# FT2232H.net
KiCad netlist of a schematic drawn in Altium Designer
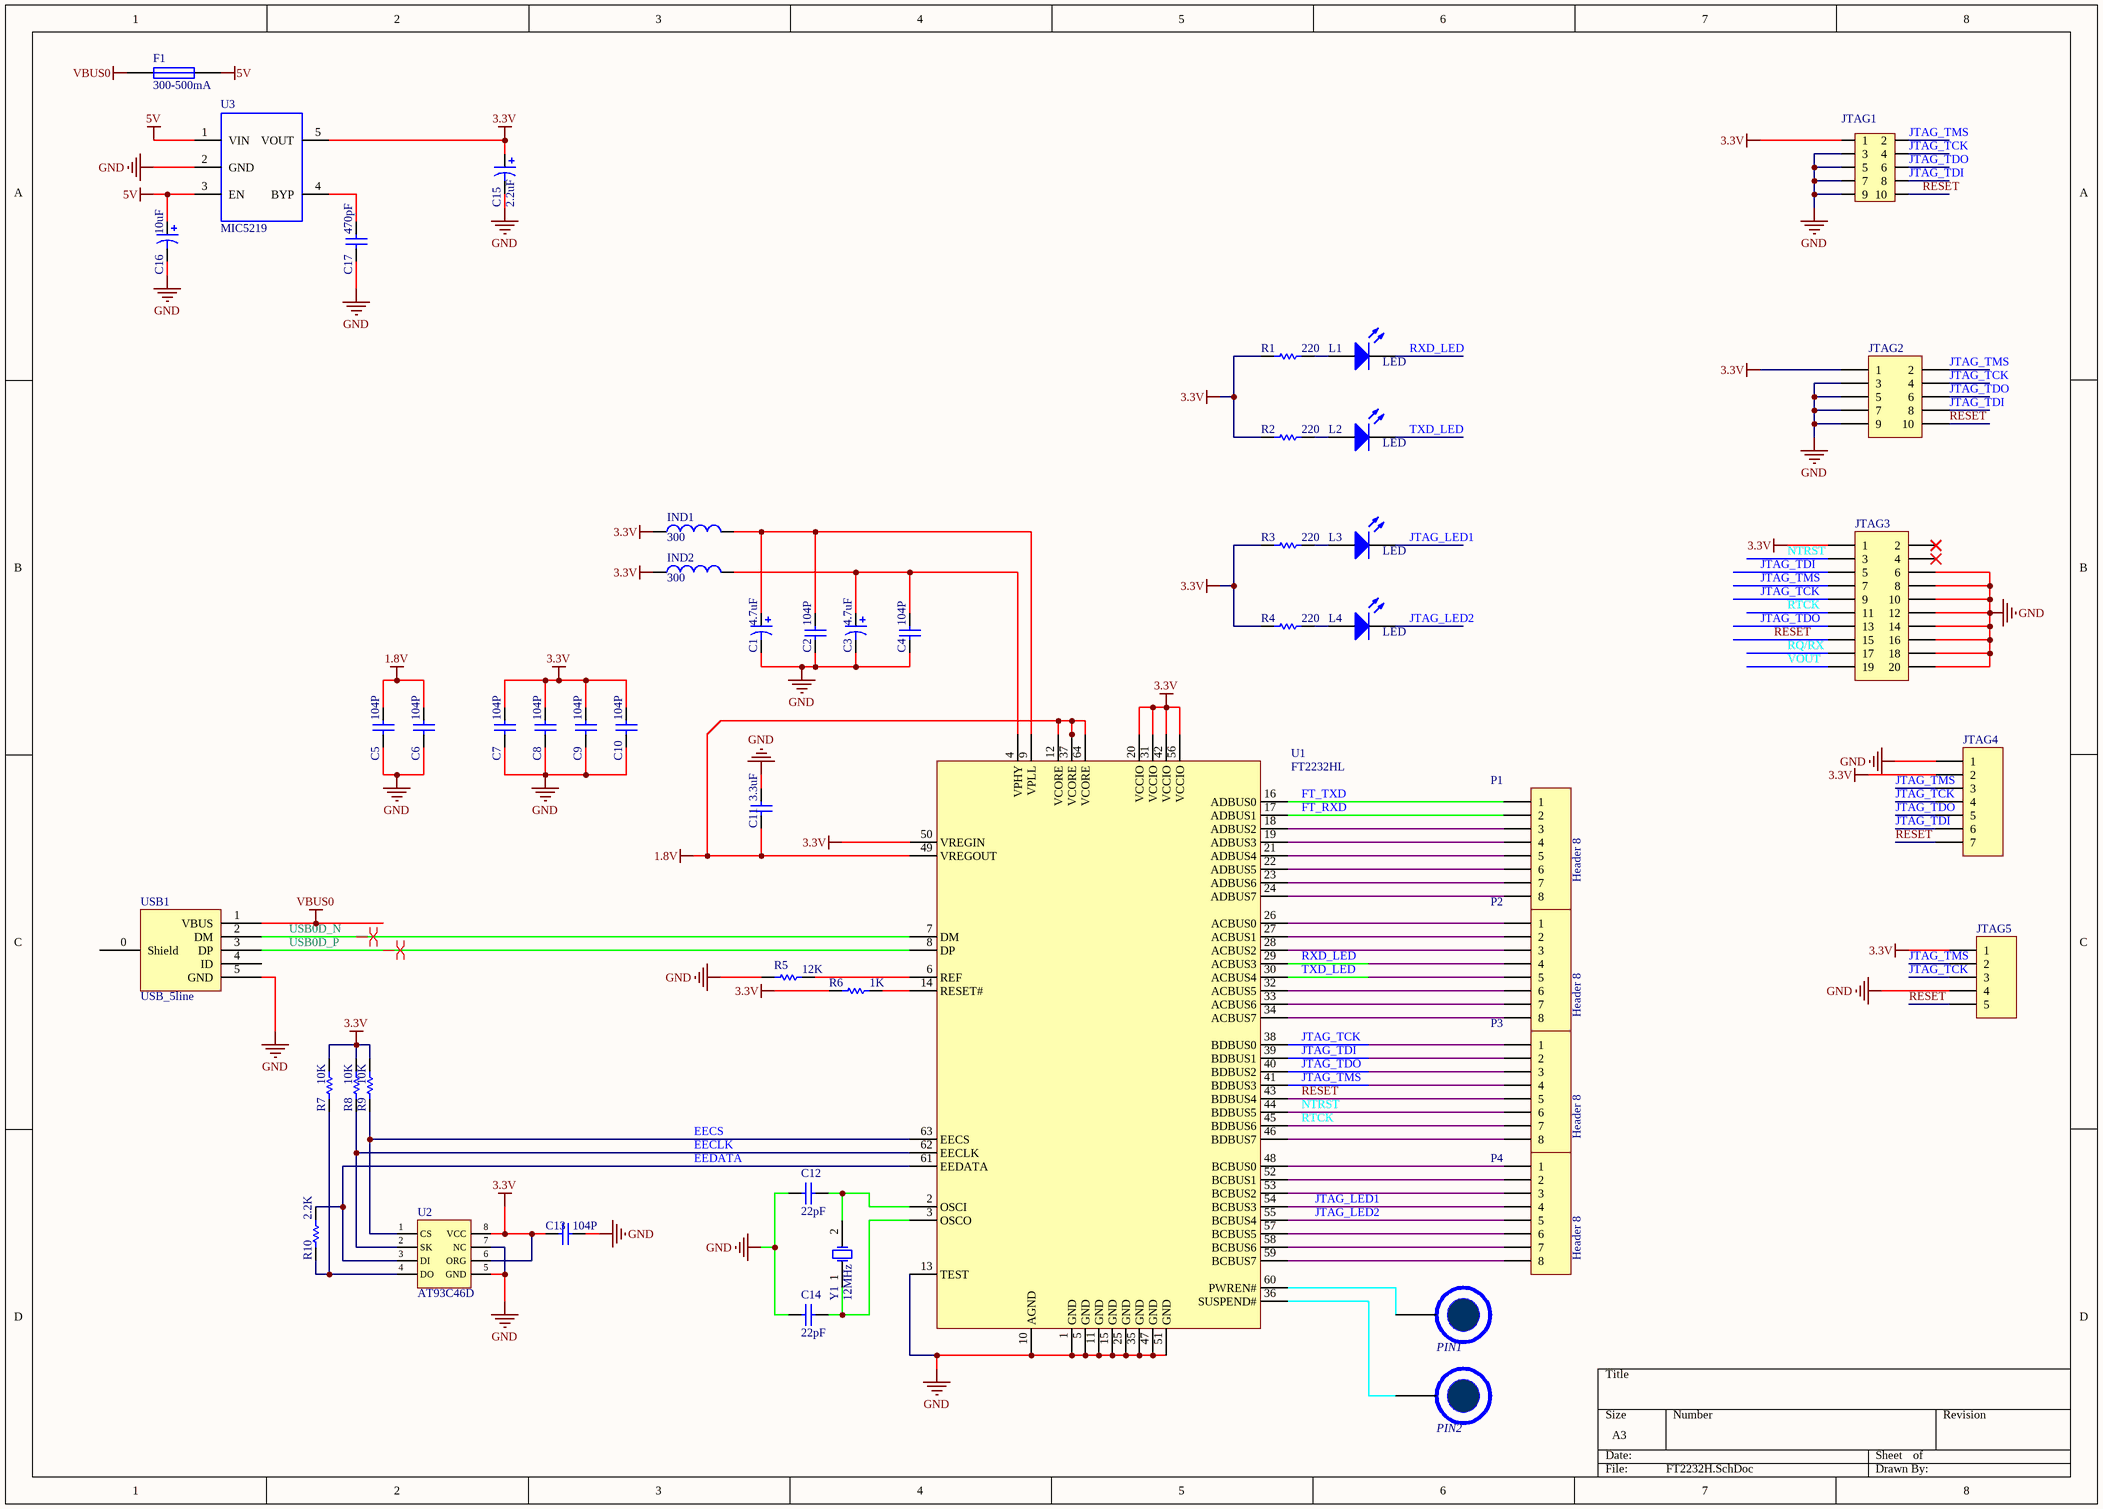
[diagram p0: FT2232H.SchDoc]

(export (version "E")
  (design (tool "Eeschema 10.0.6"))
  (components
    (comp (ref "C1")
      (value "4.7uF")
      (footprint "1608[0603]")
      (description "Polarized Capacitor (Radial)")
      (fields (field (name "Comment") "Cap Pol1") (field (name "PUBLISHER") "Altium Limited"))
      (libsource (lib "Miscellaneous Devices") (part "Cap Pol1"))
    )
    (comp (ref "C2")
      (value "104P")
      (footprint "1608[0603]")
      (description "贴片电容")
      (fields (field (name "Comment") "Cap") (field (name "PUBLISHER") "Altium Limited"))
      (libsource (lib "Sparks") (part "Cap"))
    )
    (comp (ref "C3")
      (value "4.7uF")
      (footprint "1608[0603]")
      (description "Polarized Capacitor (Radial)")
      (fields (field (name "Comment") "Cap Pol1") (field (name "PUBLISHER") "Altium Limited"))
      (libsource (lib "Miscellaneous Devices") (part "Cap Pol1"))
    )
    (comp (ref "C4")
      (value "104P")
      (footprint "1608[0603]")
      (description "贴片电容")
      (fields (field (name "Comment") "Cap") (field (name "PUBLISHER") "Altium Limited"))
      (libsource (lib "Sparks") (part "Cap"))
    )
    (comp (ref "C5")
      (value "104P")
      (footprint "1608[0603]")
      (description "贴片电容")
      (fields (field (name "Comment") "Cap") (field (name "PUBLISHER") "Altium Limited"))
      (libsource (lib "Sparks") (part "Cap"))
    )
    (comp (ref "C6")
      (value "104P")
      (footprint "1608[0603]")
      (description "贴片电容")
      (fields (field (name "Comment") "Cap") (field (name "PUBLISHER") "Altium Limited"))
      (libsource (lib "Sparks") (part "Cap"))
    )
    (comp (ref "C7")
      (value "104P")
      (footprint "1608[0603]")
      (description "贴片电容")
      (fields (field (name "Comment") "Cap") (field (name "PUBLISHER") "Altium Limited"))
      (libsource (lib "Sparks") (part "Cap"))
    )
    (comp (ref "C8")
      (value "104P")
      (footprint "1608[0603]")
      (description "贴片电容")
      (fields (field (name "Comment") "Cap") (field (name "PUBLISHER") "Altium Limited"))
      (libsource (lib "Sparks") (part "Cap"))
    )
    (comp (ref "C9")
      (value "104P")
      (footprint "1608[0603]")
      (description "贴片电容")
      (fields (field (name "Comment") "Cap") (field (name "PUBLISHER") "Altium Limited"))
      (libsource (lib "Sparks") (part "Cap"))
    )
    (comp (ref "C10")
      (value "104P")
      (footprint "1608[0603]")
      (description "贴片电容")
      (fields (field (name "Comment") "Cap") (field (name "PUBLISHER") "Altium Limited"))
      (libsource (lib "Sparks") (part "Cap"))
    )
    (comp (ref "C11")
      (value "3.3uF")
      (footprint "1608[0603]")
      (description "贴片电容")
      (fields (field (name "Comment") "Cap") (field (name "PUBLISHER") "Altium Limited"))
      (libsource (lib "Sparks") (part "Cap"))
    )
    (comp (ref "C12")
      (value "22pF")
      (footprint "1608[0603]")
      (description "贴片电容")
      (fields (field (name "Comment") "Cap") (field (name "PUBLISHER") "Altium Limited"))
      (libsource (lib "Sparks") (part "Cap"))
    )
    (comp (ref "C13")
      (value "104P")
      (footprint "1608[0603]")
      (description "贴片电容")
      (fields (field (name "Comment") "Cap") (field (name "PUBLISHER") "Altium Limited"))
      (libsource (lib "Sparks") (part "Cap"))
    )
    (comp (ref "C14")
      (value "22pF")
      (footprint "1608[0603]")
      (description "贴片电容")
      (fields (field (name "Comment") "Cap") (field (name "PUBLISHER") "Altium Limited"))
      (libsource (lib "Sparks") (part "Cap"))
    )
    (comp (ref "C15")
      (value "2.2uF")
      (footprint "1206(2)")
      (description "Polarized Capacitor (Radial)")
      (fields (field (name "Comment") "Cap Pol1") (field (name "PUBLISHER") "Altium Limited"))
      (libsource (lib "Miscellaneous Devices") (part "Cap Pol1"))
    )
    (comp (ref "C16")
      (value "10uF")
      (footprint "1206(2)")
      (description "Polarized Capacitor (Radial)")
      (fields (field (name "Comment") "Cap Pol1") (field (name "PUBLISHER") "Altium Limited"))
      (libsource (lib "Miscellaneous Devices") (part "Cap Pol1"))
    )
    (comp (ref "C17")
      (value "470pF")
      (footprint "1608[0603]")
      (description "贴片电容")
      (fields (field (name "Comment") "Cap") (field (name "PUBLISHER") "Altium Limited"))
      (libsource (lib "Sparks") (part "Cap"))
    )
    (comp (ref "F1")
      (value "300-500mA")
      (footprint "1206(2)")
      (description "Fuse")
      (fields (field (name "PUBLISHER") "Altium Limited"))
      (libsource (lib "K60-V4.0") (part "Fuse 1"))
    )
    (comp (ref "IND1")
      (value "300")
      (footprint "1608[0603]")
      (description "Inductor")
      (fields (field (name "PUBLISHER") "Altium Limited"))
      (libsource (lib "Miscellaneous Devices") (part "Inductor"))
    )
    (comp (ref "IND2")
      (value "300")
      (footprint "1608[0603]")
      (description "Inductor")
      (fields (field (name "PUBLISHER") "Altium Limited"))
      (libsource (lib "Miscellaneous Devices") (part "Inductor"))
    )
    (comp (ref "JTAG1")
      (value "Header 5X2")
      (footprint "IDC5X2")
      (description "Header, 5-Pin, Dual row")
      (libsource (lib "K60-V4.0") (part "Header 5X2"))
    )
    (comp (ref "JTAG2")
      (value "MHDR2X5")
      (footprint "MHDR2X5")
      (description "Header, 5-Pin, Dual row")
      (fields (field (name "PUBLISHER") "Altium Limited"))
      (libsource (lib "Miscellaneous Connectors") (part "MHDR2X5"))
    )
    (comp (ref "JTAG3")
      (value "Header 10X2")
      (footprint "HDR2X10")
      (description "Header, 10-Pin, Dual row")
      (fields (field (name "PUBLISHER") "Altium Limited"))
      (libsource (lib "Sparks") (part "Header 10X2"))
    )
    (comp (ref "JTAG4")
      (value "MHDR1X7")
      (footprint "MHDR1X7")
      (description "Header, 7-Pin")
      (fields (field (name "PUBLISHER") "Altium Limited"))
      (libsource (lib "Miscellaneous Connectors") (part "MHDR1X7"))
    )
    (comp (ref "JTAG5")
      (value "Header 5")
      (footprint "HDR1X5")
      (description "Header, 5-Pin")
      (fields (field (name "PUBLISHER") "Altium Limited"))
      (libsource (lib "Miscellaneous Connectors") (part "Header 5"))
    )
    (comp (ref "L1") (value "LED") (footprint "1608[0603]") (libsource (lib "Sparks") (part "LED")))
    (comp (ref "L2") (value "LED") (footprint "1608[0603]") (libsource (lib "Sparks") (part "LED")))
    (comp (ref "L3") (value "LED") (footprint "1608[0603]") (libsource (lib "Sparks") (part "LED")))
    (comp (ref "L4") (value "LED") (footprint "1608[0603]") (libsource (lib "Sparks") (part "LED")))
    (comp (ref "P1")
      (value "Header 8")
      (footprint "HDR1X8")
      (description "Header, 8-Pin")
      (fields (field (name "PUBLISHER") "Altium Limited"))
      (libsource (lib "Sparks") (part "Header 8"))
    )
    (comp (ref "P2")
      (value "Header 8")
      (footprint "HDR1X8")
      (description "Header, 8-Pin")
      (fields (field (name "PUBLISHER") "Altium Limited"))
      (libsource (lib "Sparks") (part "Header 8"))
    )
    (comp (ref "P3")
      (value "Header 8")
      (footprint "HDR1X8")
      (description "Header, 8-Pin")
      (fields (field (name "PUBLISHER") "Altium Limited"))
      (libsource (lib "Sparks") (part "Header 8"))
    )
    (comp (ref "P4")
      (value "Header 8")
      (footprint "HDR1X8")
      (description "Header, 8-Pin")
      (fields (field (name "PUBLISHER") "Altium Limited"))
      (libsource (lib "Sparks") (part "Header 8"))
    )
    (comp (ref "PIN1") (value "PIN") (footprint "PIN") (libsource (lib "2号库") (part "PIN")))
    (comp (ref "PIN2") (value "PIN") (footprint "PIN") (libsource (lib "2号库") (part "PIN")))
    (comp (ref "R1")
      (value "220")
      (footprint "1608[0603]")
      (description "贴片电阻")
      (fields (field (name "Comment") "Res") (field (name "PUBLISHER") "Altium Limited"))
      (libsource (lib "Sparks") (part "Res"))
    )
    (comp (ref "R2")
      (value "220")
      (footprint "1608[0603]")
      (description "贴片电阻")
      (fields (field (name "Comment") "Res") (field (name "PUBLISHER") "Altium Limited"))
      (libsource (lib "Sparks") (part "Res"))
    )
    (comp (ref "R3")
      (value "220")
      (footprint "1608[0603]")
      (description "贴片电阻")
      (fields (field (name "Comment") "Res") (field (name "PUBLISHER") "Altium Limited"))
      (libsource (lib "Sparks") (part "Res"))
    )
    (comp (ref "R4")
      (value "220")
      (footprint "1608[0603]")
      (description "贴片电阻")
      (fields (field (name "Comment") "Res") (field (name "PUBLISHER") "Altium Limited"))
      (libsource (lib "Sparks") (part "Res"))
    )
    (comp (ref "R5")
      (value "12K")
      (footprint "1608[0603]")
      (description "贴片电阻")
      (fields (field (name "Comment") "Res") (field (name "PUBLISHER") "Altium Limited"))
      (libsource (lib "Sparks") (part "Res"))
    )
    (comp (ref "R6")
      (value "1K")
      (footprint "1608[0603]")
      (description "贴片电阻")
      (fields (field (name "Comment") "Res") (field (name "PUBLISHER") "Altium Limited"))
      (libsource (lib "Sparks") (part "Res"))
    )
    (comp (ref "R7")
      (value "10K")
      (footprint "1608[0603]")
      (description "贴片电阻")
      (fields (field (name "Comment") "Res") (field (name "PUBLISHER") "Altium Limited"))
      (libsource (lib "Sparks") (part "Res"))
    )
    (comp (ref "R8")
      (value "10K")
      (footprint "1608[0603]")
      (description "贴片电阻")
      (fields (field (name "Comment") "Res") (field (name "PUBLISHER") "Altium Limited"))
      (libsource (lib "Sparks") (part "Res"))
    )
    (comp (ref "R9")
      (value "10K")
      (footprint "1608[0603]")
      (description "贴片电阻")
      (fields (field (name "Comment") "Res") (field (name "PUBLISHER") "Altium Limited"))
      (libsource (lib "Sparks") (part "Res"))
    )
    (comp (ref "R10")
      (value "2.2K")
      (footprint "1608[0603]")
      (description "贴片电阻")
      (fields (field (name "Comment") "Res") (field (name "PUBLISHER") "Altium Limited"))
      (libsource (lib "Sparks") (part "Res"))
    )
    (comp (ref "U1") (value "FT2232HL") (footprint "LQFP-64") (libsource (lib "2号库") (part "FT2232HL")))
    (comp (ref "U2")
      (value "AT93C46D")
      (footprint "TSOP65P640X120-8N-AT93C46D")
      (libsource (lib "2号库") (part "AT93C46D"))
    )
    (comp (ref "U3")
      (value "MIC5219")
      (footprint "SOT-23-5")
      (description "LDO")
      (libsource (lib "K60-V4.0") (part "MIC5219"))
    )
    (comp (ref "USB1")
      (value "USB_5line")
      (footprint "USB-MICRO-5P-2F")
      (libsource (lib "2号库") (part "USB_5line"))
    )
    (comp (ref "Y1")
      (value "12MHz")
      (footprint "5032")
      (description "晶体振荡器")
      (fields (field (name "PUBLISHER") "Altium Limited"))
      (libsource (lib "Sparks") (part "XTAL"))
    )
  )
  (nets
    (net (code "1") (name "/EECLK") (class "Default")
      (node (ref "R8") (pin "2") (pinfunction "2_2") (pintype "passive"))
      (node (ref "U1") (pin "62") (pinfunction "EECLK_62") (pintype "passive"))
      (node (ref "U2") (pin "2") (pinfunction "SK_2") (pintype "passive"))
    )
    (net (code "2") (name "/EECS") (class "Default")
      (node (ref "R9") (pin "2") (pinfunction "2_2") (pintype "passive"))
      (node (ref "U1") (pin "63") (pinfunction "EECS_63") (pintype "passive"))
      (node (ref "U2") (pin "1") (pinfunction "CS_1") (pintype "passive"))
    )
    (net (code "3") (name "/EEDATA") (class "Default")
      (node (ref "R10") (pin "1") (pinfunction "1_1") (pintype "passive"))
      (node (ref "U1") (pin "61") (pinfunction "EEDATA_61") (pintype "passive"))
      (node (ref "U2") (pin "3") (pinfunction "DI_3") (pintype "passive"))
    )
    (net (code "4") (name "/FT_RXD") (class "Default")
      (node (ref "P1") (pin "2") (pinfunction "2_2") (pintype "passive"))
      (node (ref "U1") (pin "17") (pinfunction "ADBUS1_17") (pintype "passive"))
    )
    (net (code "5") (name "/FT_TXD") (class "Default")
      (node (ref "P1") (pin "1") (pinfunction "1_1") (pintype "passive"))
      (node (ref "U1") (pin "16") (pinfunction "ADBUS0_16") (pintype "passive"))
    )
    (net (code "6") (name "/JTAG_LED1") (class "Default")
      (node (ref "L3") (pin "2") (pinfunction "K_2") (pintype "passive"))
      (node (ref "P4") (pin "4") (pinfunction "4_4") (pintype "passive"))
      (node (ref "U1") (pin "54") (pinfunction "BCBUS3_54") (pintype "passive"))
    )
    (net (code "7") (name "/JTAG_LED2") (class "Default")
      (node (ref "L4") (pin "2") (pinfunction "K_2") (pintype "passive"))
      (node (ref "P4") (pin "5") (pinfunction "5_5") (pintype "passive"))
      (node (ref "U1") (pin "55") (pinfunction "BCBUS4_55") (pintype "passive"))
    )
    (net (code "8") (name "/JTAG_TCK") (class "Default")
      (node (ref "JTAG1") (pin "4") (pinfunction "4_4") (pintype "passive"))
      (node (ref "JTAG2") (pin "4") (pinfunction "4_4") (pintype "passive"))
      (node (ref "JTAG3") (pin "9") (pinfunction "9_9") (pintype "passive"))
      (node (ref "JTAG4") (pin "4") (pinfunction "4_4") (pintype "passive"))
      (node (ref "JTAG5") (pin "3") (pinfunction "3_3") (pintype "passive"))
      (node (ref "P3") (pin "1") (pinfunction "1_1") (pintype "passive"))
      (node (ref "U1") (pin "38") (pinfunction "BDBUS0_38") (pintype "passive"))
    )
    (net (code "9") (name "/JTAG_TDI") (class "Default")
      (node (ref "JTAG1") (pin "8") (pinfunction "8_8") (pintype "passive"))
      (node (ref "JTAG2") (pin "8") (pinfunction "8_8") (pintype "passive"))
      (node (ref "JTAG3") (pin "5") (pinfunction "5_5") (pintype "passive"))
      (node (ref "JTAG4") (pin "6") (pinfunction "6_6") (pintype "passive"))
      (node (ref "P3") (pin "2") (pinfunction "2_2") (pintype "passive"))
      (node (ref "U1") (pin "39") (pinfunction "BDBUS1_39") (pintype "passive"))
    )
    (net (code "10") (name "/JTAG_TDO") (class "Default")
      (node (ref "JTAG1") (pin "6") (pinfunction "6_6") (pintype "passive"))
      (node (ref "JTAG2") (pin "6") (pinfunction "6_6") (pintype "passive"))
      (node (ref "JTAG3") (pin "13") (pinfunction "13_13") (pintype "passive"))
      (node (ref "JTAG4") (pin "5") (pinfunction "5_5") (pintype "passive"))
      (node (ref "P3") (pin "3") (pinfunction "3_3") (pintype "passive"))
      (node (ref "U1") (pin "40") (pinfunction "BDBUS2_40") (pintype "passive"))
    )
    (net (code "11") (name "/JTAG_TMS") (class "Default")
      (node (ref "JTAG1") (pin "2") (pinfunction "2_2") (pintype "passive"))
      (node (ref "JTAG2") (pin "2") (pinfunction "2_2") (pintype "passive"))
      (node (ref "JTAG3") (pin "7") (pinfunction "7_7") (pintype "passive"))
      (node (ref "JTAG4") (pin "3") (pinfunction "3_3") (pintype "passive"))
      (node (ref "JTAG5") (pin "2") (pinfunction "2_2") (pintype "passive"))
      (node (ref "P3") (pin "4") (pinfunction "4_4") (pintype "passive"))
      (node (ref "U1") (pin "41") (pinfunction "BDBUS3_41") (pintype "passive"))
    )
    (net (code "12") (name "/NTRST") (class "Default")
      (node (ref "JTAG3") (pin "3") (pinfunction "3_3") (pintype "passive"))
      (node (ref "P3") (pin "6") (pinfunction "6_6") (pintype "passive"))
      (node (ref "U1") (pin "44") (pinfunction "BDBUS5_44") (pintype "passive"))
    )
    (net (code "13") (name "/RESET") (class "Default")
      (node (ref "JTAG1") (pin "10") (pinfunction "10_10") (pintype "passive"))
      (node (ref "JTAG2") (pin "10") (pinfunction "10_10") (pintype "passive"))
      (node (ref "JTAG3") (pin "15") (pinfunction "15_15") (pintype "passive"))
      (node (ref "JTAG4") (pin "7") (pinfunction "7_7") (pintype "passive"))
      (node (ref "JTAG5") (pin "5") (pinfunction "5_5") (pintype "passive"))
      (node (ref "P3") (pin "5") (pinfunction "5_5") (pintype "passive"))
      (node (ref "U1") (pin "43") (pinfunction "BDBUS4_43") (pintype "passive"))
    )
    (net (code "14") (name "/RQ{slash}RX") (class "Default")
      (node (ref "JTAG3") (pin "17") (pinfunction "17_17") (pintype "passive"))
    )
    (net (code "15") (name "/RTCK") (class "Default")
      (node (ref "JTAG3") (pin "11") (pinfunction "11_11") (pintype "passive"))
      (node (ref "P3") (pin "7") (pinfunction "7_7") (pintype "passive"))
      (node (ref "U1") (pin "45") (pinfunction "BDBUS6_45") (pintype "passive"))
    )
    (net (code "16") (name "/RXD_LED") (class "Default")
      (node (ref "L1") (pin "2") (pinfunction "K_2") (pintype "passive"))
      (node (ref "P2") (pin "4") (pinfunction "4_4") (pintype "passive"))
      (node (ref "U1") (pin "29") (pinfunction "ACBUS3_29") (pintype "passive"))
    )
    (net (code "17") (name "/TXD_LED") (class "Default")
      (node (ref "L2") (pin "2") (pinfunction "K_2") (pintype "passive"))
      (node (ref "P2") (pin "5") (pinfunction "5_5") (pintype "passive"))
      (node (ref "U1") (pin "30") (pinfunction "ACBUS4_30") (pintype "passive"))
    )
    (net (code "18") (name "/USB0D_N") (class "Default")
      (node (ref "U1") (pin "7") (pinfunction "DM_7") (pintype "passive"))
      (node (ref "USB1") (pin "2") (pinfunction "DM_2") (pintype "passive"))
    )
    (net (code "19") (name "/USB0D_P") (class "Default")
      (node (ref "U1") (pin "8") (pinfunction "DP_8") (pintype "passive"))
      (node (ref "USB1") (pin "3") (pinfunction "DP_3") (pintype "passive"))
    )
    (net (code "20") (name "/VOUT") (class "Default")
      (node (ref "JTAG3") (pin "19") (pinfunction "19_19") (pintype "passive"))
    )
    (net (code "21") (name "1.8V") (class "Default")
      (node (ref "C11") (pin "1") (pinfunction "1_1") (pintype "passive"))
      (node (ref "C5") (pin "2") (pinfunction "2_2") (pintype "passive"))
      (node (ref "C6") (pin "2") (pinfunction "2_2") (pintype "passive"))
      (node (ref "U1") (pin "12") (pinfunction "VCORE_12") (pintype "passive"))
      (node (ref "U1") (pin "37") (pinfunction "VCORE_37") (pintype "passive"))
      (node (ref "U1") (pin "49") (pinfunction "VREGOUT_49") (pintype "passive"))
      (node (ref "U1") (pin "64") (pinfunction "VCORE_64") (pintype "passive"))
    )
    (net (code "22") (name "3.3V") (class "Default")
      (node (ref "C10") (pin "2") (pinfunction "2_2") (pintype "passive"))
      (node (ref "C13") (pin "2") (pinfunction "2_2") (pintype "passive"))
      (node (ref "C15") (pin "1") (pinfunction "1_1") (pintype "passive"))
      (node (ref "C7") (pin "2") (pinfunction "2_2") (pintype "passive"))
      (node (ref "C8") (pin "2") (pinfunction "2_2") (pintype "passive"))
      (node (ref "C9") (pin "2") (pinfunction "2_2") (pintype "passive"))
      (node (ref "IND1") (pin "1") (pinfunction "1_1") (pintype "passive"))
      (node (ref "IND2") (pin "1") (pinfunction "1_1") (pintype "passive"))
      (node (ref "JTAG1") (pin "1") (pinfunction "1_1") (pintype "passive"))
      (node (ref "JTAG2") (pin "1") (pinfunction "1_1") (pintype "passive"))
      (node (ref "JTAG3") (pin "1") (pinfunction "1_1") (pintype "passive"))
      (node (ref "JTAG4") (pin "2") (pinfunction "2_2") (pintype "passive"))
      (node (ref "JTAG5") (pin "1") (pinfunction "1_1") (pintype "passive"))
      (node (ref "R1") (pin "2") (pinfunction "2_2") (pintype "passive"))
      (node (ref "R2") (pin "2") (pinfunction "2_2") (pintype "passive"))
      (node (ref "R3") (pin "2") (pinfunction "2_2") (pintype "passive"))
      (node (ref "R4") (pin "2") (pinfunction "2_2") (pintype "passive"))
      (node (ref "R6") (pin "2") (pinfunction "2_2") (pintype "passive"))
      (node (ref "R7") (pin "1") (pinfunction "1_1") (pintype "passive"))
      (node (ref "R8") (pin "1") (pinfunction "1_1") (pintype "passive"))
      (node (ref "R9") (pin "1") (pinfunction "1_1") (pintype "passive"))
      (node (ref "U1") (pin "20") (pinfunction "VCCIO_20") (pintype "passive"))
      (node (ref "U1") (pin "31") (pinfunction "VCCIO_31") (pintype "passive"))
      (node (ref "U1") (pin "42") (pinfunction "VCCIO_42") (pintype "passive"))
      (node (ref "U1") (pin "50") (pinfunction "VREGIN_50") (pintype "passive"))
      (node (ref "U1") (pin "56") (pinfunction "VCCIO_56") (pintype "passive"))
      (node (ref "U2") (pin "6") (pinfunction "ORG_6") (pintype "passive"))
      (node (ref "U2") (pin "8") (pinfunction "VCC_8") (pintype "passive"))
      (node (ref "U3") (pin "5") (pinfunction "VOUT_5") (pintype "passive"))
    )
    (net (code "23") (name "5V") (class "Default")
      (node (ref "C16") (pin "1") (pinfunction "1_1") (pintype "passive"))
      (node (ref "F1") (pin "2") (pinfunction "2_2") (pintype "passive"))
      (node (ref "U3") (pin "1") (pinfunction "VIN_1") (pintype "passive"))
      (node (ref "U3") (pin "3") (pinfunction "EN_3") (pintype "passive"))
    )
    (net (code "24") (name "GND") (class "Default")
      (node (ref "C1") (pin "2") (pinfunction "2_2") (pintype "passive"))
      (node (ref "C10") (pin "1") (pinfunction "1_1") (pintype "passive"))
      (node (ref "C11") (pin "2") (pinfunction "2_2") (pintype "passive"))
      (node (ref "C12") (pin "1") (pinfunction "1_1") (pintype "passive"))
      (node (ref "C13") (pin "1") (pinfunction "1_1") (pintype "passive"))
      (node (ref "C14") (pin "2") (pinfunction "2_2") (pintype "passive"))
      (node (ref "C15") (pin "2") (pinfunction "2_2") (pintype "passive"))
      (node (ref "C16") (pin "2") (pinfunction "2_2") (pintype "passive"))
      (node (ref "C17") (pin "1") (pinfunction "1_1") (pintype "passive"))
      (node (ref "C2") (pin "1") (pinfunction "1_1") (pintype "passive"))
      (node (ref "C3") (pin "2") (pinfunction "2_2") (pintype "passive"))
      (node (ref "C4") (pin "1") (pinfunction "1_1") (pintype "passive"))
      (node (ref "C5") (pin "1") (pinfunction "1_1") (pintype "passive"))
      (node (ref "C6") (pin "1") (pinfunction "1_1") (pintype "passive"))
      (node (ref "C7") (pin "1") (pinfunction "1_1") (pintype "passive"))
      (node (ref "C8") (pin "1") (pinfunction "1_1") (pintype "passive"))
      (node (ref "C9") (pin "1") (pinfunction "1_1") (pintype "passive"))
      (node (ref "JTAG1") (pin "3") (pinfunction "3_3") (pintype "passive"))
      (node (ref "JTAG1") (pin "5") (pinfunction "5_5") (pintype "passive"))
      (node (ref "JTAG1") (pin "7") (pinfunction "7_7") (pintype "passive"))
      (node (ref "JTAG1") (pin "9") (pinfunction "9_9") (pintype "passive"))
      (node (ref "JTAG2") (pin "3") (pinfunction "3_3") (pintype "passive"))
      (node (ref "JTAG2") (pin "5") (pinfunction "5_5") (pintype "passive"))
      (node (ref "JTAG2") (pin "7") (pinfunction "7_7") (pintype "passive"))
      (node (ref "JTAG2") (pin "9") (pinfunction "9_9") (pintype "passive"))
      (node (ref "JTAG3") (pin "10") (pinfunction "10_10") (pintype "passive"))
      (node (ref "JTAG3") (pin "12") (pinfunction "12_12") (pintype "passive"))
      (node (ref "JTAG3") (pin "14") (pinfunction "14_14") (pintype "passive"))
      (node (ref "JTAG3") (pin "16") (pinfunction "16_16") (pintype "passive"))
      (node (ref "JTAG3") (pin "18") (pinfunction "18_18") (pintype "passive"))
      (node (ref "JTAG3") (pin "20") (pinfunction "20_20") (pintype "passive"))
      (node (ref "JTAG3") (pin "6") (pinfunction "6_6") (pintype "passive"))
      (node (ref "JTAG3") (pin "8") (pinfunction "8_8") (pintype "passive"))
      (node (ref "JTAG4") (pin "1") (pinfunction "1_1") (pintype "passive"))
      (node (ref "JTAG5") (pin "4") (pinfunction "4_4") (pintype "passive"))
      (node (ref "R5") (pin "2") (pinfunction "2_2") (pintype "passive"))
      (node (ref "U1") (pin "1") (pinfunction "GND_1") (pintype "passive"))
      (node (ref "U1") (pin "10") (pinfunction "AGND_10") (pintype "passive"))
      (node (ref "U1") (pin "11") (pinfunction "GND_11") (pintype "passive"))
      (node (ref "U1") (pin "13") (pinfunction "TEST_13") (pintype "passive"))
      (node (ref "U1") (pin "15") (pinfunction "GND_15") (pintype "passive"))
      (node (ref "U1") (pin "25") (pinfunction "GND_25") (pintype "passive"))
      (node (ref "U1") (pin "35") (pinfunction "GND_35") (pintype "passive"))
      (node (ref "U1") (pin "47") (pinfunction "GND_47") (pintype "passive"))
      (node (ref "U1") (pin "5") (pinfunction "GND_5") (pintype "passive"))
      (node (ref "U1") (pin "51") (pinfunction "GND_51") (pintype "passive"))
      (node (ref "U2") (pin "5") (pinfunction "GND_5") (pintype "passive"))
      (node (ref "U2") (pin "7") (pinfunction "NC_7") (pintype "passive"))
      (node (ref "U3") (pin "2") (pinfunction "GND_2") (pintype "passive"))
      (node (ref "USB1") (pin "5") (pinfunction "GND_5") (pintype "passive"))
    )
    (net (code "25") (name "Net-(L1-A)") (class "Default")
      (node (ref "L1") (pin "1") (pinfunction "A_1") (pintype "passive"))
      (node (ref "R1") (pin "1") (pinfunction "1_1") (pintype "passive"))
    )
    (net (code "26") (name "Net-(L2-A)") (class "Default")
      (node (ref "L2") (pin "1") (pinfunction "A_1") (pintype "passive"))
      (node (ref "R2") (pin "1") (pinfunction "1_1") (pintype "passive"))
    )
    (net (code "27") (name "Net-(L3-A)") (class "Default")
      (node (ref "L3") (pin "1") (pinfunction "A_1") (pintype "passive"))
      (node (ref "R3") (pin "1") (pinfunction "1_1") (pintype "passive"))
    )
    (net (code "28") (name "Net-(L4-A)") (class "Default")
      (node (ref "L4") (pin "1") (pinfunction "A_1") (pintype "passive"))
      (node (ref "R4") (pin "1") (pinfunction "1_1") (pintype "passive"))
    )
    (net (code "29") (name "Net-(PIN1-PIN)") (class "Default")
      (node (ref "PIN1") (pin "1") (pinfunction "PIN_1") (pintype "passive"))
      (node (ref "U1") (pin "60") (pinfunction "PWREN#_60") (pintype "passive"))
    )
    (net (code "30") (name "Net-(PIN2-PIN)") (class "Default")
      (node (ref "PIN2") (pin "1") (pinfunction "PIN_1") (pintype "passive"))
      (node (ref "U1") (pin "36") (pinfunction "SUSPEND#_36") (pintype "passive"))
    )
    (net (code "31") (name "Net-(U1-ACBUS0)") (class "Default")
      (node (ref "P2") (pin "1") (pinfunction "1_1") (pintype "passive"))
      (node (ref "U1") (pin "26") (pinfunction "ACBUS0_26") (pintype "passive"))
    )
    (net (code "32") (name "Net-(U1-ACBUS1)") (class "Default")
      (node (ref "P2") (pin "2") (pinfunction "2_2") (pintype "passive"))
      (node (ref "U1") (pin "27") (pinfunction "ACBUS1_27") (pintype "passive"))
    )
    (net (code "33") (name "Net-(U1-ACBUS2)") (class "Default")
      (node (ref "P2") (pin "3") (pinfunction "3_3") (pintype "passive"))
      (node (ref "U1") (pin "28") (pinfunction "ACBUS2_28") (pintype "passive"))
    )
    (net (code "34") (name "Net-(U1-ACBUS5)") (class "Default")
      (node (ref "P2") (pin "6") (pinfunction "6_6") (pintype "passive"))
      (node (ref "U1") (pin "32") (pinfunction "ACBUS5_32") (pintype "passive"))
    )
    (net (code "35") (name "Net-(U1-ACBUS6)") (class "Default")
      (node (ref "P2") (pin "7") (pinfunction "7_7") (pintype "passive"))
      (node (ref "U1") (pin "33") (pinfunction "ACBUS6_33") (pintype "passive"))
    )
    (net (code "36") (name "Net-(U1-ACBUS7)") (class "Default")
      (node (ref "P2") (pin "8") (pinfunction "8_8") (pintype "passive"))
      (node (ref "U1") (pin "34") (pinfunction "ACBUS7_34") (pintype "passive"))
    )
    (net (code "37") (name "Net-(U1-ADBUS2)") (class "Default")
      (node (ref "P1") (pin "3") (pinfunction "3_3") (pintype "passive"))
      (node (ref "U1") (pin "18") (pinfunction "ADBUS2_18") (pintype "passive"))
    )
    (net (code "38") (name "Net-(U1-ADBUS3)") (class "Default")
      (node (ref "P1") (pin "4") (pinfunction "4_4") (pintype "passive"))
      (node (ref "U1") (pin "19") (pinfunction "ADBUS3_19") (pintype "passive"))
    )
    (net (code "39") (name "Net-(U1-ADBUS4)") (class "Default")
      (node (ref "P1") (pin "5") (pinfunction "5_5") (pintype "passive"))
      (node (ref "U1") (pin "21") (pinfunction "ADBUS4_21") (pintype "passive"))
    )
    (net (code "40") (name "Net-(U1-ADBUS5)") (class "Default")
      (node (ref "P1") (pin "6") (pinfunction "6_6") (pintype "passive"))
      (node (ref "U1") (pin "22") (pinfunction "ADBUS5_22") (pintype "passive"))
    )
    (net (code "41") (name "Net-(U1-ADBUS6)") (class "Default")
      (node (ref "P1") (pin "7") (pinfunction "7_7") (pintype "passive"))
      (node (ref "U1") (pin "23") (pinfunction "ADBUS6_23") (pintype "passive"))
    )
    (net (code "42") (name "Net-(U1-ADBUS7)") (class "Default")
      (node (ref "P1") (pin "8") (pinfunction "8_8") (pintype "passive"))
      (node (ref "U1") (pin "24") (pinfunction "ADBUS7_24") (pintype "passive"))
    )
    (net (code "43") (name "Net-(U1-BCBUS0)") (class "Default")
      (node (ref "P4") (pin "1") (pinfunction "1_1") (pintype "passive"))
      (node (ref "U1") (pin "48") (pinfunction "BCBUS0_48") (pintype "passive"))
    )
    (net (code "44") (name "Net-(U1-BCBUS1)") (class "Default")
      (node (ref "P4") (pin "2") (pinfunction "2_2") (pintype "passive"))
      (node (ref "U1") (pin "52") (pinfunction "BCBUS1_52") (pintype "passive"))
    )
    (net (code "45") (name "Net-(U1-BCBUS2)") (class "Default")
      (node (ref "P4") (pin "3") (pinfunction "3_3") (pintype "passive"))
      (node (ref "U1") (pin "53") (pinfunction "BCBUS2_53") (pintype "passive"))
    )
    (net (code "46") (name "Net-(U1-BCBUS5)") (class "Default")
      (node (ref "P4") (pin "6") (pinfunction "6_6") (pintype "passive"))
      (node (ref "U1") (pin "57") (pinfunction "BCBUS5_57") (pintype "passive"))
    )
    (net (code "47") (name "Net-(U1-BCBUS6)") (class "Default")
      (node (ref "P4") (pin "7") (pinfunction "7_7") (pintype "passive"))
      (node (ref "U1") (pin "58") (pinfunction "BCBUS6_58") (pintype "passive"))
    )
    (net (code "48") (name "Net-(U1-BCBUS7)") (class "Default")
      (node (ref "P4") (pin "8") (pinfunction "8_8") (pintype "passive"))
      (node (ref "U1") (pin "59") (pinfunction "BCBUS7_59") (pintype "passive"))
    )
    (net (code "49") (name "Net-(U1-BDBUS7)") (class "Default")
      (node (ref "P3") (pin "8") (pinfunction "8_8") (pintype "passive"))
      (node (ref "U1") (pin "46") (pinfunction "BDBUS7_46") (pintype "passive"))
    )
    (net (code "50") (name "Net-(U1-OSCI)") (class "Default")
      (node (ref "C12") (pin "2") (pinfunction "2_2") (pintype "passive"))
      (node (ref "U1") (pin "2") (pinfunction "OSCI_2") (pintype "passive"))
      (node (ref "Y1") (pin "2") (pinfunction "OSC2_2") (pintype "passive"))
    )
    (net (code "51") (name "Net-(U1-OSCO)") (class "Default")
      (node (ref "C14") (pin "1") (pinfunction "1_1") (pintype "passive"))
      (node (ref "U1") (pin "3") (pinfunction "OSCO_3") (pintype "passive"))
      (node (ref "Y1") (pin "1") (pinfunction "OSC1_1") (pintype "passive"))
    )
    (net (code "52") (name "Net-(U1-REF)") (class "Default")
      (node (ref "R5") (pin "1") (pinfunction "1_1") (pintype "passive"))
      (node (ref "U1") (pin "6") (pinfunction "REF_6") (pintype "passive"))
    )
    (net (code "53") (name "Net-(U1-RESET#)") (class "Default")
      (node (ref "R6") (pin "1") (pinfunction "1_1") (pintype "passive"))
      (node (ref "U1") (pin "14") (pinfunction "RESET#_14") (pintype "passive"))
    )
    (net (code "54") (name "Net-(U1-VPHY)") (class "Default")
      (node (ref "C3") (pin "1") (pinfunction "1_1") (pintype "passive"))
      (node (ref "C4") (pin "2") (pinfunction "2_2") (pintype "passive"))
      (node (ref "IND2") (pin "2") (pinfunction "2_2") (pintype "passive"))
      (node (ref "U1") (pin "4") (pinfunction "VPHY_4") (pintype "passive"))
    )
    (net (code "55") (name "Net-(U1-VPLL)") (class "Default")
      (node (ref "C1") (pin "1") (pinfunction "1_1") (pintype "passive"))
      (node (ref "C2") (pin "2") (pinfunction "2_2") (pintype "passive"))
      (node (ref "IND1") (pin "2") (pinfunction "2_2") (pintype "passive"))
      (node (ref "U1") (pin "9") (pinfunction "VPLL_9") (pintype "passive"))
    )
    (net (code "56") (name "Net-(U2-DO)") (class "Default")
      (node (ref "R10") (pin "2") (pinfunction "2_2") (pintype "passive"))
      (node (ref "R7") (pin "2") (pinfunction "2_2") (pintype "passive"))
      (node (ref "U2") (pin "4") (pinfunction "DO_4") (pintype "passive"))
    )
    (net (code "57") (name "Net-(U3-BYP)") (class "Default")
      (node (ref "C17") (pin "2") (pinfunction "2_2") (pintype "passive"))
      (node (ref "U3") (pin "4") (pinfunction "BYP_4") (pintype "passive"))
    )
    (net (code "58") (name "VBUS0") (class "Default")
      (node (ref "F1") (pin "1") (pinfunction "1_1") (pintype "passive"))
      (node (ref "USB1") (pin "1") (pinfunction "VBUS_1") (pintype "passive"))
    )
    (net (code "59") (name "unconnected-(JTAG3-Pad2)") (class "Default")
      (node (ref "JTAG3") (pin "2") (pinfunction "2_2") (pintype "passive+no_connect"))
    )
    (net (code "60") (name "unconnected-(JTAG3-Pad4)") (class "Default")
      (node (ref "JTAG3") (pin "4") (pinfunction "4_4") (pintype "passive+no_connect"))
    )
    (net (code "61") (name "unconnected-(USB1-ID-Pad4)") (class "Default")
      (node (ref "USB1") (pin "4") (pinfunction "ID_4") (pintype "passive"))
    )
    (net (code "62") (name "unconnected-(USB1-Shield-Pad0)") (class "Default")
      (node (ref "USB1") (pin "0") (pinfunction "Shield_0") (pintype "passive"))
    )
  )
)
